# versao2.net
KiCad netlist of a schematic drawn in EAGLE
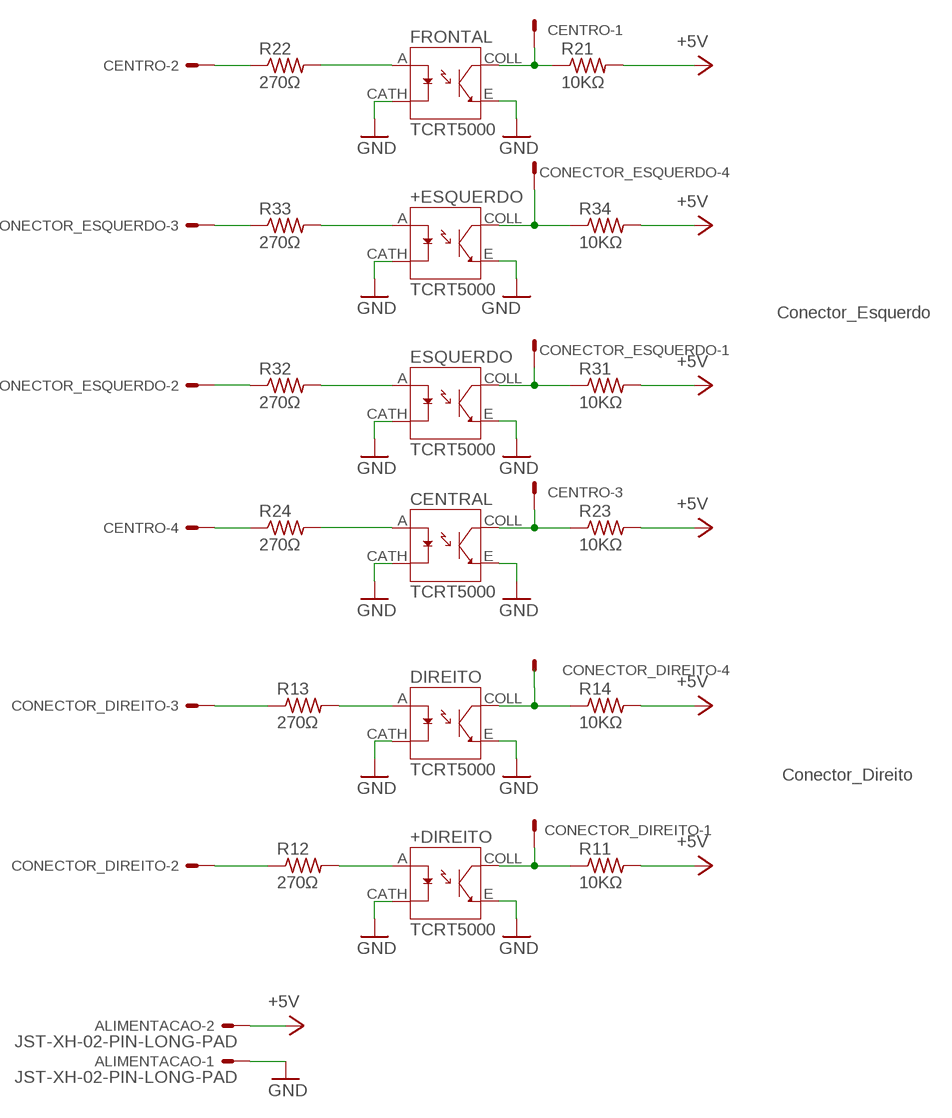
[diagram p0: schematic, sheet 1]

(export (version "E")
  (design (tool "Eeschema 10.0.6"))
  (components
    (comp (ref "+DIREITO")
      (value "TCRT5000")
      (footprint "eagle-import:OPTO_TCRT5000")
      (fields (field (name "MF") "Vishay"))
      (libsource (lib "eagle-import") (part "TCRT5000"))
    )
    (comp (ref "+ESQUERDO")
      (value "TCRT5000")
      (footprint "eagle-import:OPTO_TCRT5000")
      (fields (field (name "MF") "Vishay"))
      (libsource (lib "eagle-import") (part "TCRT5000"))
    )
    (comp (ref "ALIMENTACAO")
      (value "JST-XH-02-PIN-LONG-PAD")
      (footprint "eagle-import:JST-XH-02-PACKAGE-LONG-PAD")
      (libsource (lib "eagle-import") (part "JST-XH-02-PIN-LONG-PAD"))
    )
    (comp (ref "CENTRAL")
      (value "TCRT5000")
      (footprint "eagle-import:OPTO_TCRT5000")
      (fields (field (name "MF") "Vishay"))
      (libsource (lib "eagle-import") (part "TCRT5000"))
    )
    (comp (ref "CENTRO")
      (value "JST-XH-04-PIN-LONG-PAD")
      (footprint "eagle-import:JST-XH-04-PACKAGE-LONG-PAD")
      (libsource (lib "eagle-import") (part "JST-XH-04-PIN-LONG-PAD"))
    )
    (comp (ref "CONECTOR_DIREITO")
      (value "Conector_Direito")
      (footprint "eagle-import:JST-XH-04-PACKAGE-LONG-PAD")
      (libsource (lib "eagle-import") (part "JST-XH-04-PIN-LONG-PAD"))
    )
    (comp (ref "CONECTOR_ESQUERDO")
      (value "Conector_Esquerdo")
      (footprint "eagle-import:JST-XH-04-PACKAGE-LONG-PAD")
      (libsource (lib "eagle-import") (part "JST-XH-04-PIN-LONG-PAD"))
    )
    (comp (ref "DIREITO")
      (value "TCRT5000")
      (footprint "eagle-import:OPTO_TCRT5000")
      (fields (field (name "MF") "Vishay"))
      (libsource (lib "eagle-import") (part "TCRT5000"))
    )
    (comp (ref "ESQUERDO")
      (value "TCRT5000")
      (footprint "eagle-import:OPTO_TCRT5000")
      (fields (field (name "MF") "Vishay"))
      (libsource (lib "eagle-import") (part "TCRT5000"))
    )
    (comp (ref "FRONTAL")
      (value "TCRT5000")
      (footprint "eagle-import:OPTO_TCRT5000")
      (fields (field (name "MF") "Vishay"))
      (libsource (lib "eagle-import") (part "TCRT5000"))
    )
    (comp (ref "R11")
      (value "10KΩ")
      (footprint "eagle-import:0204_7")
      (libsource (lib "eagle-import") (part "R-US_0204/7"))
    )
    (comp (ref "R12")
      (value "270Ω")
      (footprint "eagle-import:0204_7")
      (libsource (lib "eagle-import") (part "R-US_0204/7"))
    )
    (comp (ref "R13")
      (value "270Ω")
      (footprint "eagle-import:0204_7")
      (libsource (lib "eagle-import") (part "R-US_0204/7"))
    )
    (comp (ref "R14")
      (value "10KΩ")
      (footprint "eagle-import:0204_7")
      (libsource (lib "eagle-import") (part "R-US_0204/7"))
    )
    (comp (ref "R21")
      (value "10KΩ")
      (footprint "eagle-import:0204_7")
      (libsource (lib "eagle-import") (part "R-US_0204/7"))
    )
    (comp (ref "R22")
      (value "270Ω")
      (footprint "eagle-import:0204_7")
      (libsource (lib "eagle-import") (part "R-US_0204/7"))
    )
    (comp (ref "R23")
      (value "10KΩ")
      (footprint "eagle-import:0204_7")
      (libsource (lib "eagle-import") (part "R-US_0204/7"))
    )
    (comp (ref "R24")
      (value "270Ω")
      (footprint "eagle-import:0204_7")
      (libsource (lib "eagle-import") (part "R-US_0204/7"))
    )
    (comp (ref "R31")
      (value "10KΩ")
      (footprint "eagle-import:0204_7")
      (libsource (lib "eagle-import") (part "R-US_0204/7"))
    )
    (comp (ref "R32")
      (value "270Ω")
      (footprint "eagle-import:0204_7")
      (libsource (lib "eagle-import") (part "R-US_0204/7"))
    )
    (comp (ref "R33")
      (value "270Ω")
      (footprint "eagle-import:0204_7")
      (libsource (lib "eagle-import") (part "R-US_0204/7"))
    )
    (comp (ref "R34")
      (value "10KΩ")
      (footprint "eagle-import:0204_7")
      (libsource (lib "eagle-import") (part "R-US_0204/7"))
    )
  )
  (nets
    (net (code "1") (name "+5V") (class "Default")
      (node (ref "ALIMENTACAO") (pin "2") (pinfunction "S_2") (pintype "passive"))
      (node (ref "R11") (pin "2") (pinfunction "2_2") (pintype "passive"))
      (node (ref "R14") (pin "2") (pinfunction "2_2") (pintype "passive"))
      (node (ref "R21") (pin "2") (pinfunction "2_2") (pintype "passive"))
      (node (ref "R23") (pin "2") (pinfunction "2_2") (pintype "passive"))
      (node (ref "R31") (pin "2") (pinfunction "2_2") (pintype "passive"))
      (node (ref "R34") (pin "2") (pinfunction "2_2") (pintype "passive"))
    )
    (net (code "2") (name "GND") (class "Default")
      (node (ref "+DIREITO") (pin "CATH") (pinfunction "CATH_CATH") (pintype "passive"))
      (node (ref "+DIREITO") (pin "E") (pinfunction "E_E") (pintype "passive"))
      (node (ref "+ESQUERDO") (pin "CATH") (pinfunction "CATH_CATH") (pintype "passive"))
      (node (ref "+ESQUERDO") (pin "E") (pinfunction "E_E") (pintype "passive"))
      (node (ref "ALIMENTACAO") (pin "1") (pinfunction "S_1") (pintype "passive"))
      (node (ref "CENTRAL") (pin "CATH") (pinfunction "CATH_CATH") (pintype "passive"))
      (node (ref "CENTRAL") (pin "E") (pinfunction "E_E") (pintype "passive"))
      (node (ref "DIREITO") (pin "CATH") (pinfunction "CATH_CATH") (pintype "passive"))
      (node (ref "DIREITO") (pin "E") (pinfunction "E_E") (pintype "passive"))
      (node (ref "ESQUERDO") (pin "CATH") (pinfunction "CATH_CATH") (pintype "passive"))
      (node (ref "ESQUERDO") (pin "E") (pinfunction "E_E") (pintype "passive"))
      (node (ref "FRONTAL") (pin "CATH") (pinfunction "CATH_CATH") (pintype "passive"))
      (node (ref "FRONTAL") (pin "E") (pinfunction "E_E") (pintype "passive"))
    )
    (net (code "3") (name "Net-(+DIREITO-PadA)") (class "Default")
      (node (ref "+DIREITO") (pin "A") (pinfunction "A_A") (pintype "passive"))
      (node (ref "R12") (pin "2") (pinfunction "2_2") (pintype "passive"))
    )
    (net (code "4") (name "Net-(+ESQUERDO-PadA)") (class "Default")
      (node (ref "+ESQUERDO") (pin "A") (pinfunction "A_A") (pintype "passive"))
      (node (ref "R33") (pin "2") (pinfunction "2_2") (pintype "passive"))
    )
    (net (code "5") (name "Net-(CENTRAL-PadA)") (class "Default")
      (node (ref "CENTRAL") (pin "A") (pinfunction "A_A") (pintype "passive"))
      (node (ref "R24") (pin "2") (pinfunction "2_2") (pintype "passive"))
    )
    (net (code "6") (name "Net-(CENTROA-S)") (class "Default")
      (node (ref "CENTRO") (pin "1") (pinfunction "S_1") (pintype "passive"))
      (node (ref "FRONTAL") (pin "COLL") (pinfunction "COLL_COLL") (pintype "passive"))
      (node (ref "R21") (pin "1") (pinfunction "1_1") (pintype "passive"))
    )
    (net (code "7") (name "Net-(CENTROB-S)") (class "Default")
      (node (ref "CENTRO") (pin "2") (pinfunction "S_2") (pintype "passive"))
      (node (ref "R22") (pin "1") (pinfunction "1_1") (pintype "passive"))
    )
    (net (code "8") (name "Net-(CENTROC-S)") (class "Default")
      (node (ref "CENTRAL") (pin "COLL") (pinfunction "COLL_COLL") (pintype "passive"))
      (node (ref "CENTRO") (pin "3") (pinfunction "S_3") (pintype "passive"))
      (node (ref "R23") (pin "1") (pinfunction "1_1") (pintype "passive"))
    )
    (net (code "9") (name "Net-(CENTROD-S)") (class "Default")
      (node (ref "CENTRO") (pin "4") (pinfunction "S_4") (pintype "passive"))
      (node (ref "R24") (pin "1") (pinfunction "1_1") (pintype "passive"))
    )
    (net (code "10") (name "Net-(CONECTOR_DIREITOA-S)") (class "Default")
      (node (ref "+DIREITO") (pin "COLL") (pinfunction "COLL_COLL") (pintype "passive"))
      (node (ref "CONECTOR_DIREITO") (pin "1") (pinfunction "S_1") (pintype "passive"))
      (node (ref "R11") (pin "1") (pinfunction "1_1") (pintype "passive"))
    )
    (net (code "11") (name "Net-(CONECTOR_DIREITOB-S)") (class "Default")
      (node (ref "CONECTOR_DIREITO") (pin "2") (pinfunction "S_2") (pintype "passive"))
      (node (ref "R12") (pin "1") (pinfunction "1_1") (pintype "passive"))
    )
    (net (code "12") (name "Net-(CONECTOR_DIREITOC-S)") (class "Default")
      (node (ref "CONECTOR_DIREITO") (pin "3") (pinfunction "S_3") (pintype "passive"))
      (node (ref "R13") (pin "1") (pinfunction "1_1") (pintype "passive"))
    )
    (net (code "13") (name "Net-(CONECTOR_DIREITOD-S)") (class "Default")
      (node (ref "CONECTOR_DIREITO") (pin "4") (pinfunction "S_4") (pintype "passive"))
      (node (ref "DIREITO") (pin "COLL") (pinfunction "COLL_COLL") (pintype "passive"))
      (node (ref "R14") (pin "1") (pinfunction "1_1") (pintype "passive"))
    )
    (net (code "14") (name "Net-(CONECTOR_ESQUERDOA-S)") (class "Default")
      (node (ref "CONECTOR_ESQUERDO") (pin "1") (pinfunction "S_1") (pintype "passive"))
      (node (ref "ESQUERDO") (pin "COLL") (pinfunction "COLL_COLL") (pintype "passive"))
      (node (ref "R31") (pin "1") (pinfunction "1_1") (pintype "passive"))
    )
    (net (code "15") (name "Net-(CONECTOR_ESQUERDOB-S)") (class "Default")
      (node (ref "CONECTOR_ESQUERDO") (pin "2") (pinfunction "S_2") (pintype "passive"))
      (node (ref "R32") (pin "1") (pinfunction "1_1") (pintype "passive"))
    )
    (net (code "16") (name "Net-(CONECTOR_ESQUERDOC-S)") (class "Default")
      (node (ref "CONECTOR_ESQUERDO") (pin "3") (pinfunction "S_3") (pintype "passive"))
      (node (ref "R33") (pin "1") (pinfunction "1_1") (pintype "passive"))
    )
    (net (code "17") (name "Net-(CONECTOR_ESQUERDOD-S)") (class "Default")
      (node (ref "+ESQUERDO") (pin "COLL") (pinfunction "COLL_COLL") (pintype "passive"))
      (node (ref "CONECTOR_ESQUERDO") (pin "4") (pinfunction "S_4") (pintype "passive"))
      (node (ref "R34") (pin "1") (pinfunction "1_1") (pintype "passive"))
    )
    (net (code "18") (name "Net-(DIREITO-PadA)") (class "Default")
      (node (ref "DIREITO") (pin "A") (pinfunction "A_A") (pintype "passive"))
      (node (ref "R13") (pin "2") (pinfunction "2_2") (pintype "passive"))
    )
    (net (code "19") (name "Net-(ESQUERDO-PadA)") (class "Default")
      (node (ref "ESQUERDO") (pin "A") (pinfunction "A_A") (pintype "passive"))
      (node (ref "R32") (pin "2") (pinfunction "2_2") (pintype "passive"))
    )
    (net (code "20") (name "Net-(FRONTAL-PadA)") (class "Default")
      (node (ref "FRONTAL") (pin "A") (pinfunction "A_A") (pintype "passive"))
      (node (ref "R22") (pin "2") (pinfunction "2_2") (pintype "passive"))
    )
  )
)
